# joysticks_keyboard.net
KiCad netlist of a schematic drawn in EAGLE
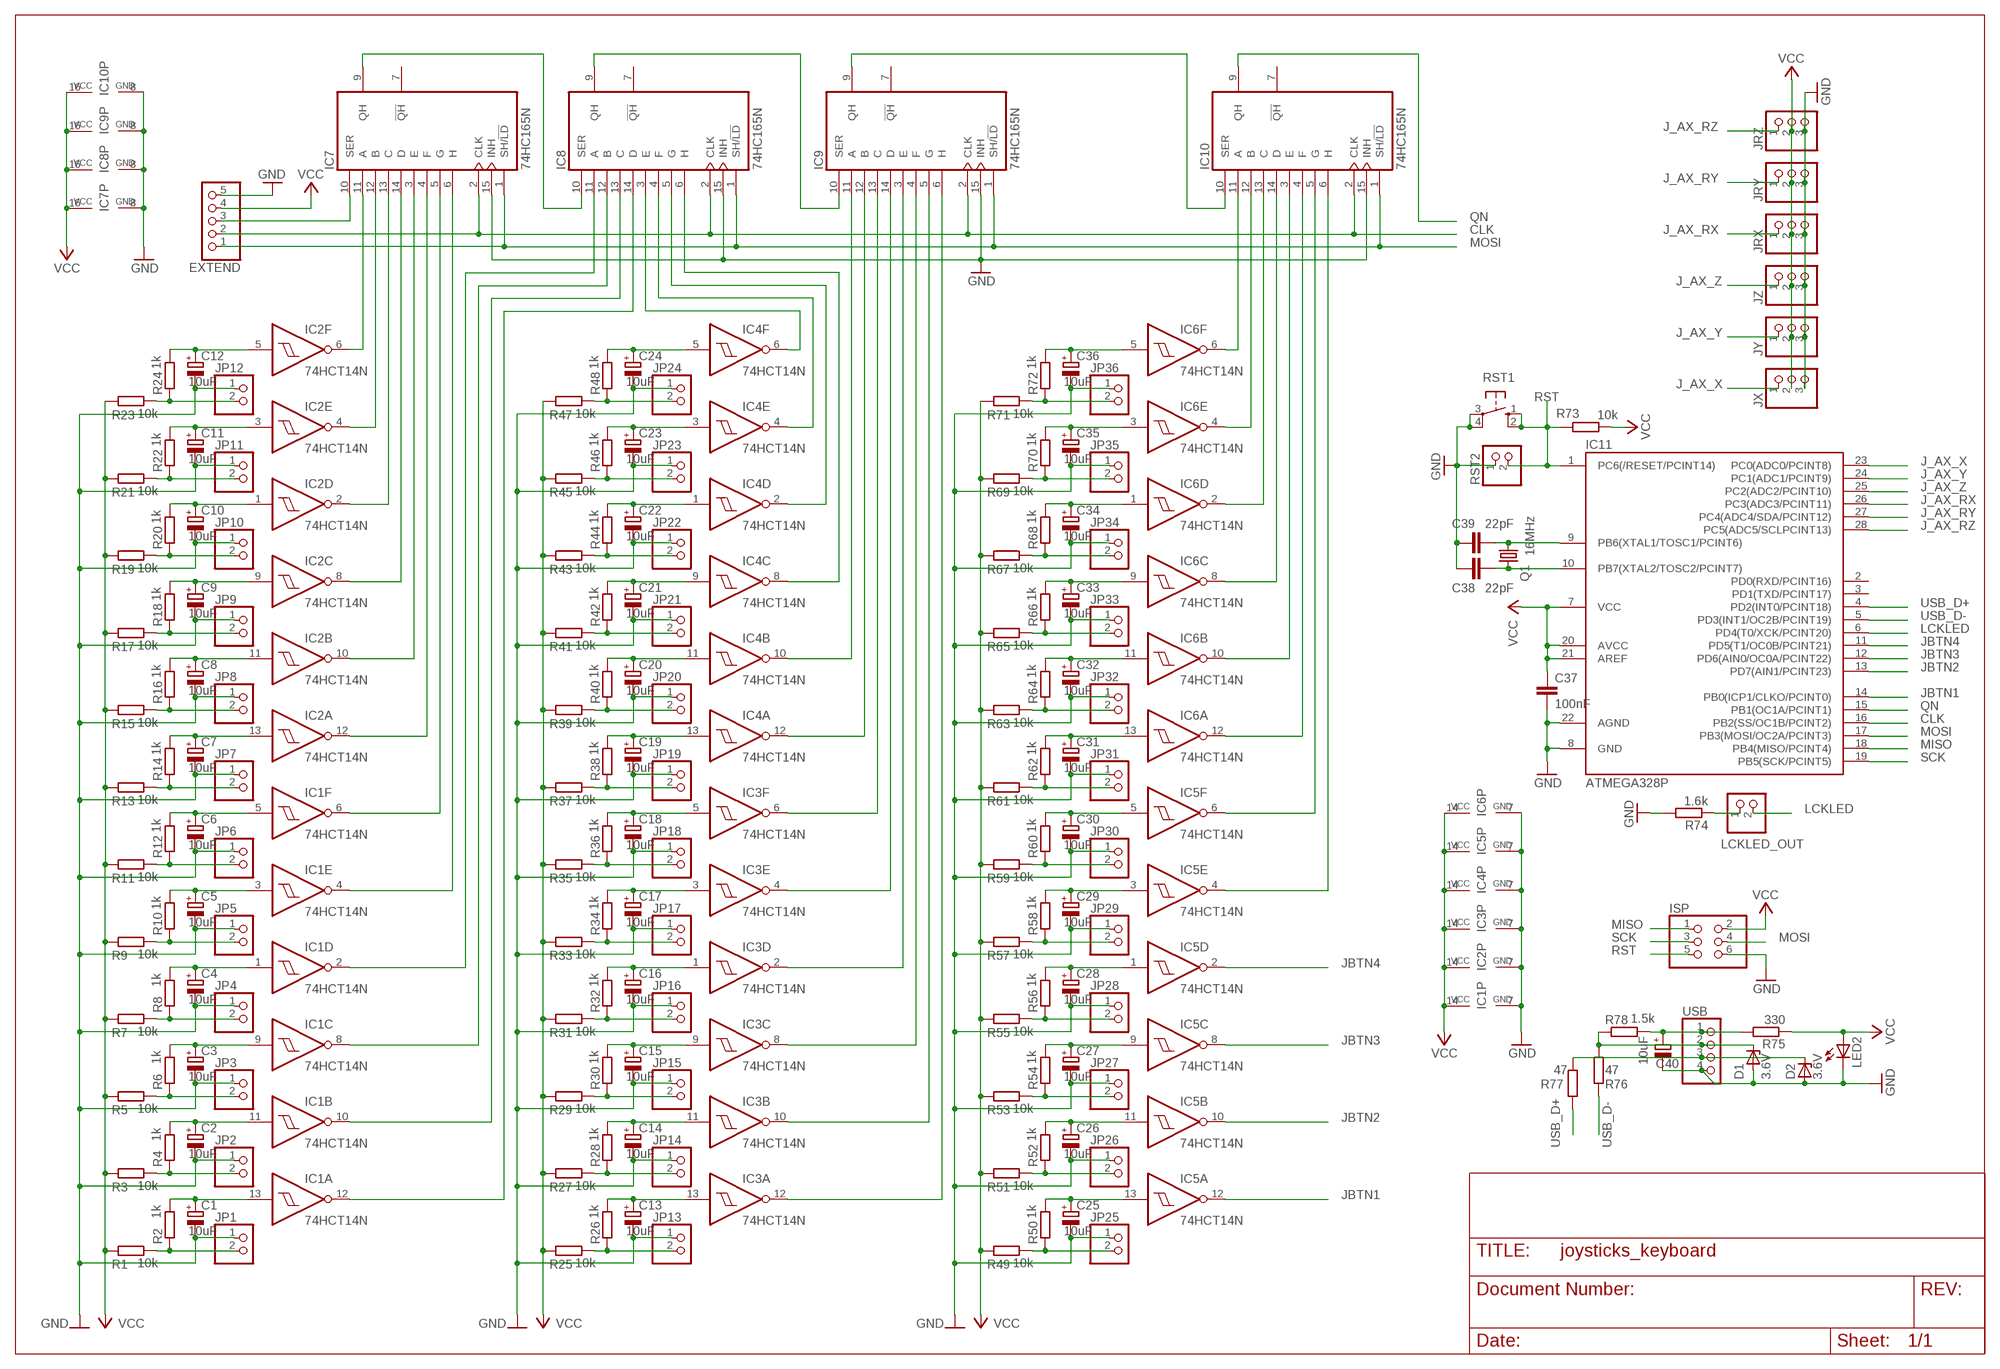
[diagram p0: schematic, sheet 1]

(export (version "E")
  (design (tool "Eeschema 10.0.6"))
  (components
    (comp (ref "C1")
      (value "10uF")
      (footprint "eagle-import:E2-5")
      (libsource (lib "eagle-import") (part "CPOL-EUE2-5"))
    )
    (comp (ref "C2")
      (value "10uF")
      (footprint "eagle-import:E2-5")
      (libsource (lib "eagle-import") (part "CPOL-EUE2-5"))
    )
    (comp (ref "C3")
      (value "10uF")
      (footprint "eagle-import:E2-5")
      (libsource (lib "eagle-import") (part "CPOL-EUE2-5"))
    )
    (comp (ref "C4")
      (value "10uF")
      (footprint "eagle-import:E2-5")
      (libsource (lib "eagle-import") (part "CPOL-EUE2-5"))
    )
    (comp (ref "C5")
      (value "10uF")
      (footprint "eagle-import:E2-5")
      (libsource (lib "eagle-import") (part "CPOL-EUE2-5"))
    )
    (comp (ref "C6")
      (value "10uF")
      (footprint "eagle-import:E2-5")
      (libsource (lib "eagle-import") (part "CPOL-EUE2-5"))
    )
    (comp (ref "C7")
      (value "10uF")
      (footprint "eagle-import:E2-5")
      (libsource (lib "eagle-import") (part "CPOL-EUE2-5"))
    )
    (comp (ref "C8")
      (value "10uF")
      (footprint "eagle-import:E2-5")
      (libsource (lib "eagle-import") (part "CPOL-EUE2-5"))
    )
    (comp (ref "C9")
      (value "10uF")
      (footprint "eagle-import:E2-5")
      (libsource (lib "eagle-import") (part "CPOL-EUE2-5"))
    )
    (comp (ref "C10")
      (value "10uF")
      (footprint "eagle-import:E2-5")
      (libsource (lib "eagle-import") (part "CPOL-EUE2-5"))
    )
    (comp (ref "C11")
      (value "10uF")
      (footprint "eagle-import:E2-5")
      (libsource (lib "eagle-import") (part "CPOL-EUE2-5"))
    )
    (comp (ref "C12")
      (value "10uF")
      (footprint "eagle-import:E2-5")
      (libsource (lib "eagle-import") (part "CPOL-EUE2-5"))
    )
    (comp (ref "C13")
      (value "10uF")
      (footprint "eagle-import:E2-5")
      (libsource (lib "eagle-import") (part "CPOL-EUE2-5"))
    )
    (comp (ref "C14")
      (value "10uF")
      (footprint "eagle-import:E2-5")
      (libsource (lib "eagle-import") (part "CPOL-EUE2-5"))
    )
    (comp (ref "C15")
      (value "10uF")
      (footprint "eagle-import:E2-5")
      (libsource (lib "eagle-import") (part "CPOL-EUE2-5"))
    )
    (comp (ref "C16")
      (value "10uF")
      (footprint "eagle-import:E2-5")
      (libsource (lib "eagle-import") (part "CPOL-EUE2-5"))
    )
    (comp (ref "C17")
      (value "10uF")
      (footprint "eagle-import:E2-5")
      (libsource (lib "eagle-import") (part "CPOL-EUE2-5"))
    )
    (comp (ref "C18")
      (value "10uF")
      (footprint "eagle-import:E2-5")
      (libsource (lib "eagle-import") (part "CPOL-EUE2-5"))
    )
    (comp (ref "C19")
      (value "10uF")
      (footprint "eagle-import:E2-5")
      (libsource (lib "eagle-import") (part "CPOL-EUE2-5"))
    )
    (comp (ref "C20")
      (value "10uF")
      (footprint "eagle-import:E2-5")
      (libsource (lib "eagle-import") (part "CPOL-EUE2-5"))
    )
    (comp (ref "C21")
      (value "10uF")
      (footprint "eagle-import:E2-5")
      (libsource (lib "eagle-import") (part "CPOL-EUE2-5"))
    )
    (comp (ref "C22")
      (value "10uF")
      (footprint "eagle-import:E2-5")
      (libsource (lib "eagle-import") (part "CPOL-EUE2-5"))
    )
    (comp (ref "C23")
      (value "10uF")
      (footprint "eagle-import:E2-5")
      (libsource (lib "eagle-import") (part "CPOL-EUE2-5"))
    )
    (comp (ref "C24")
      (value "10uF")
      (footprint "eagle-import:E2-5")
      (libsource (lib "eagle-import") (part "CPOL-EUE2-5"))
    )
    (comp (ref "C25")
      (value "10uF")
      (footprint "eagle-import:E2-5")
      (libsource (lib "eagle-import") (part "CPOL-EUE2-5"))
    )
    (comp (ref "C26")
      (value "10uF")
      (footprint "eagle-import:E2-5")
      (libsource (lib "eagle-import") (part "CPOL-EUE2-5"))
    )
    (comp (ref "C27")
      (value "10uF")
      (footprint "eagle-import:E2-5")
      (libsource (lib "eagle-import") (part "CPOL-EUE2-5"))
    )
    (comp (ref "C28")
      (value "10uF")
      (footprint "eagle-import:E2-5")
      (libsource (lib "eagle-import") (part "CPOL-EUE2-5"))
    )
    (comp (ref "C29")
      (value "10uF")
      (footprint "eagle-import:E2-5")
      (libsource (lib "eagle-import") (part "CPOL-EUE2-5"))
    )
    (comp (ref "C30")
      (value "10uF")
      (footprint "eagle-import:E2-5")
      (libsource (lib "eagle-import") (part "CPOL-EUE2-5"))
    )
    (comp (ref "C31")
      (value "10uF")
      (footprint "eagle-import:E2-5")
      (libsource (lib "eagle-import") (part "CPOL-EUE2-5"))
    )
    (comp (ref "C32")
      (value "10uF")
      (footprint "eagle-import:E2-5")
      (libsource (lib "eagle-import") (part "CPOL-EUE2-5"))
    )
    (comp (ref "C33")
      (value "10uF")
      (footprint "eagle-import:E2-5")
      (libsource (lib "eagle-import") (part "CPOL-EUE2-5"))
    )
    (comp (ref "C34")
      (value "10uF")
      (footprint "eagle-import:E2-5")
      (libsource (lib "eagle-import") (part "CPOL-EUE2-5"))
    )
    (comp (ref "C35")
      (value "10uF")
      (footprint "eagle-import:E2-5")
      (libsource (lib "eagle-import") (part "CPOL-EUE2-5"))
    )
    (comp (ref "C36")
      (value "10uF")
      (footprint "eagle-import:E2-5")
      (libsource (lib "eagle-import") (part "CPOL-EUE2-5"))
    )
    (comp (ref "C37")
      (value "100nF")
      (footprint "eagle-import:C025-024X044")
      (libsource (lib "eagle-import") (part "C-EU025-024X044"))
    )
    (comp (ref "C38")
      (value "22pF")
      (footprint "eagle-import:C025-024X044")
      (libsource (lib "eagle-import") (part "C-EU025-024X044"))
    )
    (comp (ref "C39")
      (value "22pF")
      (footprint "eagle-import:C025-024X044")
      (libsource (lib "eagle-import") (part "C-EU025-024X044"))
    )
    (comp (ref "C40")
      (value "10uF")
      (footprint "eagle-import:E2,5-6E")
      (libsource (lib "eagle-import") (part "CPOL-EUE2,5-6E"))
    )
    (comp (ref "D1")
      (value "3.6V")
      (footprint "eagle-import:ZDIO-2.5")
      (libsource (lib "eagle-import") (part "ZENER-DIODEZD-2.5"))
    )
    (comp (ref "D2")
      (value "3.6V")
      (footprint "eagle-import:ZDIO-2.5")
      (libsource (lib "eagle-import") (part "ZENER-DIODEZD-2.5"))
    )
    (comp (ref "EXTEND")
      (value "PINHD-1X5")
      (footprint "eagle-import:1X05")
      (libsource (lib "eagle-import") (part "PINHD-1X5"))
    )
    (comp (ref "IC1")
      (value "74HCT14N")
      (footprint "eagle-import:DIL14")
      (libsource (lib "eagle-import") (part "7414NHCT"))
    )
    (comp (ref "IC2")
      (value "74HCT14N")
      (footprint "eagle-import:DIL14")
      (libsource (lib "eagle-import") (part "7414NHCT"))
    )
    (comp (ref "IC3")
      (value "74HCT14N")
      (footprint "eagle-import:DIL14")
      (libsource (lib "eagle-import") (part "7414NHCT"))
    )
    (comp (ref "IC4")
      (value "74HCT14N")
      (footprint "eagle-import:DIL14")
      (libsource (lib "eagle-import") (part "7414NHCT"))
    )
    (comp (ref "IC5")
      (value "74HCT14N")
      (footprint "eagle-import:DIL14")
      (libsource (lib "eagle-import") (part "7414NHCT"))
    )
    (comp (ref "IC6")
      (value "74HCT14N")
      (footprint "eagle-import:DIL14")
      (libsource (lib "eagle-import") (part "7414NHCT"))
    )
    (comp (ref "IC7")
      (value "74HC165N")
      (footprint "eagle-import:DIL16")
      (libsource (lib "eagle-import") (part "74165NHC"))
    )
    (comp (ref "IC8")
      (value "74HC165N")
      (footprint "eagle-import:DIL16")
      (libsource (lib "eagle-import") (part "74165NHC"))
    )
    (comp (ref "IC9")
      (value "74HC165N")
      (footprint "eagle-import:DIL16")
      (libsource (lib "eagle-import") (part "74165NHC"))
    )
    (comp (ref "IC10")
      (value "74HC165N")
      (footprint "eagle-import:DIL16")
      (libsource (lib "eagle-import") (part "74165NHC"))
    )
    (comp (ref "IC11")
      (value "ATMEGA328P")
      (footprint "eagle-import:DIL28-3")
      (libsource (lib "eagle-import") (part "MEGA48/88/168-PU"))
    )
    (comp (ref "ISP")
      (value "PINHD-2X3")
      (footprint "eagle-import:2X03")
      (libsource (lib "eagle-import") (part "PINHD-2X3"))
    )
    (comp (ref "JP1")
      (value "PINHD-1X2")
      (footprint "eagle-import:1X02")
      (libsource (lib "eagle-import") (part "PINHD-1X2"))
    )
    (comp (ref "JP2")
      (value "PINHD-1X2")
      (footprint "eagle-import:1X02")
      (libsource (lib "eagle-import") (part "PINHD-1X2"))
    )
    (comp (ref "JP3")
      (value "PINHD-1X2")
      (footprint "eagle-import:1X02")
      (libsource (lib "eagle-import") (part "PINHD-1X2"))
    )
    (comp (ref "JP4")
      (value "PINHD-1X2")
      (footprint "eagle-import:1X02")
      (libsource (lib "eagle-import") (part "PINHD-1X2"))
    )
    (comp (ref "JP5")
      (value "PINHD-1X2")
      (footprint "eagle-import:1X02")
      (libsource (lib "eagle-import") (part "PINHD-1X2"))
    )
    (comp (ref "JP6")
      (value "PINHD-1X2")
      (footprint "eagle-import:1X02")
      (libsource (lib "eagle-import") (part "PINHD-1X2"))
    )
    (comp (ref "JP7")
      (value "PINHD-1X2")
      (footprint "eagle-import:1X02")
      (libsource (lib "eagle-import") (part "PINHD-1X2"))
    )
    (comp (ref "JP8")
      (value "PINHD-1X2")
      (footprint "eagle-import:1X02")
      (libsource (lib "eagle-import") (part "PINHD-1X2"))
    )
    (comp (ref "JP9")
      (value "PINHD-1X2")
      (footprint "eagle-import:1X02")
      (libsource (lib "eagle-import") (part "PINHD-1X2"))
    )
    (comp (ref "JP10")
      (value "PINHD-1X2")
      (footprint "eagle-import:1X02")
      (libsource (lib "eagle-import") (part "PINHD-1X2"))
    )
    (comp (ref "JP11")
      (value "PINHD-1X2")
      (footprint "eagle-import:1X02")
      (libsource (lib "eagle-import") (part "PINHD-1X2"))
    )
    (comp (ref "JP12")
      (value "PINHD-1X2")
      (footprint "eagle-import:1X02")
      (libsource (lib "eagle-import") (part "PINHD-1X2"))
    )
    (comp (ref "JP13")
      (value "PINHD-1X2")
      (footprint "eagle-import:1X02")
      (libsource (lib "eagle-import") (part "PINHD-1X2"))
    )
    (comp (ref "JP14")
      (value "PINHD-1X2")
      (footprint "eagle-import:1X02")
      (libsource (lib "eagle-import") (part "PINHD-1X2"))
    )
    (comp (ref "JP15")
      (value "PINHD-1X2")
      (footprint "eagle-import:1X02")
      (libsource (lib "eagle-import") (part "PINHD-1X2"))
    )
    (comp (ref "JP16")
      (value "PINHD-1X2")
      (footprint "eagle-import:1X02")
      (libsource (lib "eagle-import") (part "PINHD-1X2"))
    )
    (comp (ref "JP17")
      (value "PINHD-1X2")
      (footprint "eagle-import:1X02")
      (libsource (lib "eagle-import") (part "PINHD-1X2"))
    )
    (comp (ref "JP18")
      (value "PINHD-1X2")
      (footprint "eagle-import:1X02")
      (libsource (lib "eagle-import") (part "PINHD-1X2"))
    )
    (comp (ref "JP19")
      (value "PINHD-1X2")
      (footprint "eagle-import:1X02")
      (libsource (lib "eagle-import") (part "PINHD-1X2"))
    )
    (comp (ref "JP20")
      (value "PINHD-1X2")
      (footprint "eagle-import:1X02")
      (libsource (lib "eagle-import") (part "PINHD-1X2"))
    )
    (comp (ref "JP21")
      (value "PINHD-1X2")
      (footprint "eagle-import:1X02")
      (libsource (lib "eagle-import") (part "PINHD-1X2"))
    )
    (comp (ref "JP22")
      (value "PINHD-1X2")
      (footprint "eagle-import:1X02")
      (libsource (lib "eagle-import") (part "PINHD-1X2"))
    )
    (comp (ref "JP23")
      (value "PINHD-1X2")
      (footprint "eagle-import:1X02")
      (libsource (lib "eagle-import") (part "PINHD-1X2"))
    )
    (comp (ref "JP24")
      (value "PINHD-1X2")
      (footprint "eagle-import:1X02")
      (libsource (lib "eagle-import") (part "PINHD-1X2"))
    )
    (comp (ref "JP25")
      (value "PINHD-1X2")
      (footprint "eagle-import:1X02")
      (libsource (lib "eagle-import") (part "PINHD-1X2"))
    )
    (comp (ref "JP26")
      (value "PINHD-1X2")
      (footprint "eagle-import:1X02")
      (libsource (lib "eagle-import") (part "PINHD-1X2"))
    )
    (comp (ref "JP27")
      (value "PINHD-1X2")
      (footprint "eagle-import:1X02")
      (libsource (lib "eagle-import") (part "PINHD-1X2"))
    )
    (comp (ref "JP28")
      (value "PINHD-1X2")
      (footprint "eagle-import:1X02")
      (libsource (lib "eagle-import") (part "PINHD-1X2"))
    )
    (comp (ref "JP29")
      (value "PINHD-1X2")
      (footprint "eagle-import:1X02")
      (libsource (lib "eagle-import") (part "PINHD-1X2"))
    )
    (comp (ref "JP30")
      (value "PINHD-1X2")
      (footprint "eagle-import:1X02")
      (libsource (lib "eagle-import") (part "PINHD-1X2"))
    )
    (comp (ref "JP31")
      (value "PINHD-1X2")
      (footprint "eagle-import:1X02")
      (libsource (lib "eagle-import") (part "PINHD-1X2"))
    )
    (comp (ref "JP32")
      (value "PINHD-1X2")
      (footprint "eagle-import:1X02")
      (libsource (lib "eagle-import") (part "PINHD-1X2"))
    )
    (comp (ref "JP33")
      (value "PINHD-1X2")
      (footprint "eagle-import:1X02")
      (libsource (lib "eagle-import") (part "PINHD-1X2"))
    )
    (comp (ref "JP34")
      (value "PINHD-1X2")
      (footprint "eagle-import:1X02")
      (libsource (lib "eagle-import") (part "PINHD-1X2"))
    )
    (comp (ref "JP35")
      (value "PINHD-1X2")
      (footprint "eagle-import:1X02")
      (libsource (lib "eagle-import") (part "PINHD-1X2"))
    )
    (comp (ref "JP36")
      (value "PINHD-1X2")
      (footprint "eagle-import:1X02")
      (libsource (lib "eagle-import") (part "PINHD-1X2"))
    )
    (comp (ref "JRX")
      (value "PINHD-1X3")
      (footprint "eagle-import:1X03")
      (libsource (lib "eagle-import") (part "PINHD-1X3"))
    )
    (comp (ref "JRY")
      (value "PINHD-1X3")
      (footprint "eagle-import:1X03")
      (libsource (lib "eagle-import") (part "PINHD-1X3"))
    )
    (comp (ref "JRZ")
      (value "PINHD-1X3")
      (footprint "eagle-import:1X03")
      (libsource (lib "eagle-import") (part "PINHD-1X3"))
    )
    (comp (ref "JX")
      (value "PINHD-1X3")
      (footprint "eagle-import:1X03")
      (libsource (lib "eagle-import") (part "PINHD-1X3"))
    )
    (comp (ref "JY")
      (value "PINHD-1X3")
      (footprint "eagle-import:1X03")
      (libsource (lib "eagle-import") (part "PINHD-1X3"))
    )
    (comp (ref "JZ")
      (value "PINHD-1X3")
      (footprint "eagle-import:1X03")
      (libsource (lib "eagle-import") (part "PINHD-1X3"))
    )
    (comp (ref "LCKLED_OUT")
      (value "PINHD-1X2")
      (footprint "eagle-import:1X02")
      (libsource (lib "eagle-import") (part "PINHD-1X2"))
    )
    (comp (ref "LED2")
      (value "LEDLZR181")
      (footprint "eagle-import:LZR181")
      (libsource (lib "eagle-import") (part "LEDLZR181"))
    )
    (comp (ref "Q1")
      (value "16MHz")
      (footprint "eagle-import:HC49_S")
      (libsource (lib "eagle-import") (part "CRYSTALHC49S"))
    )
    (comp (ref "R1")
      (value "10k")
      (footprint "eagle-import:0204V")
      (libsource (lib "eagle-import") (part "R-EU_0204/2V"))
    )
    (comp (ref "R2")
      (value "1k")
      (footprint "eagle-import:0204_5")
      (libsource (lib "eagle-import") (part "R-EU_0204/5"))
    )
    (comp (ref "R3")
      (value "10k")
      (footprint "eagle-import:0204V")
      (libsource (lib "eagle-import") (part "R-EU_0204/2V"))
    )
    (comp (ref "R4")
      (value "1k")
      (footprint "eagle-import:0204_5")
      (libsource (lib "eagle-import") (part "R-EU_0204/5"))
    )
    (comp (ref "R5")
      (value "10k")
      (footprint "eagle-import:0204V")
      (libsource (lib "eagle-import") (part "R-EU_0204/2V"))
    )
    (comp (ref "R6")
      (value "1k")
      (footprint "eagle-import:0204_5")
      (libsource (lib "eagle-import") (part "R-EU_0204/5"))
    )
    (comp (ref "R7")
      (value "10k")
      (footprint "eagle-import:0204V")
      (libsource (lib "eagle-import") (part "R-EU_0204/2V"))
    )
    (comp (ref "R8")
      (value "1k")
      (footprint "eagle-import:0204_5")
      (libsource (lib "eagle-import") (part "R-EU_0204/5"))
    )
    (comp (ref "R9")
      (value "10k")
      (footprint "eagle-import:0204V")
      (libsource (lib "eagle-import") (part "R-EU_0204/2V"))
    )
    (comp (ref "R10")
      (value "1k")
      (footprint "eagle-import:0204_5")
      (libsource (lib "eagle-import") (part "R-EU_0204/5"))
    )
    (comp (ref "R11")
      (value "10k")
      (footprint "eagle-import:0204V")
      (libsource (lib "eagle-import") (part "R-EU_0204/2V"))
    )
    (comp (ref "R12")
      (value "1k")
      (footprint "eagle-import:0204_5")
      (libsource (lib "eagle-import") (part "R-EU_0204/5"))
    )
    (comp (ref "R13")
      (value "10k")
      (footprint "eagle-import:0204V")
      (libsource (lib "eagle-import") (part "R-EU_0204/2V"))
    )
    (comp (ref "R14")
      (value "1k")
      (footprint "eagle-import:0204_5")
      (libsource (lib "eagle-import") (part "R-EU_0204/5"))
    )
    (comp (ref "R15")
      (value "10k")
      (footprint "eagle-import:0204V")
      (libsource (lib "eagle-import") (part "R-EU_0204/2V"))
    )
    (comp (ref "R16")
      (value "1k")
      (footprint "eagle-import:0204_5")
      (libsource (lib "eagle-import") (part "R-EU_0204/5"))
    )
    (comp (ref "R17")
      (value "10k")
      (footprint "eagle-import:0204V")
      (libsource (lib "eagle-import") (part "R-EU_0204/2V"))
    )
    (comp (ref "R18")
      (value "1k")
      (footprint "eagle-import:0204_5")
      (libsource (lib "eagle-import") (part "R-EU_0204/5"))
    )
    (comp (ref "R19")
      (value "10k")
      (footprint "eagle-import:0204V")
      (libsource (lib "eagle-import") (part "R-EU_0204/2V"))
    )
    (comp (ref "R20")
      (value "1k")
      (footprint "eagle-import:0204_5")
      (libsource (lib "eagle-import") (part "R-EU_0204/5"))
    )
    (comp (ref "R21")
      (value "10k")
      (footprint "eagle-import:0204V")
      (libsource (lib "eagle-import") (part "R-EU_0204/2V"))
    )
    (comp (ref "R22")
      (value "1k")
      (footprint "eagle-import:0204_5")
      (libsource (lib "eagle-import") (part "R-EU_0204/5"))
    )
    (comp (ref "R23")
      (value "10k")
      (footprint "eagle-import:0204V")
      (libsource (lib "eagle-import") (part "R-EU_0204/2V"))
    )
    (comp (ref "R24")
      (value "1k")
      (footprint "eagle-import:0204_5")
      (libsource (lib "eagle-import") (part "R-EU_0204/5"))
    )
    (comp (ref "R25")
      (value "10k")
      (footprint "eagle-import:0204V")
      (libsource (lib "eagle-import") (part "R-EU_0204/2V"))
    )
    (comp (ref "R26")
      (value "1k")
      (footprint "eagle-import:0204_5")
      (libsource (lib "eagle-import") (part "R-EU_0204/5"))
    )
    (comp (ref "R27")
      (value "10k")
      (footprint "eagle-import:0204V")
      (libsource (lib "eagle-import") (part "R-EU_0204/2V"))
    )
    (comp (ref "R28")
      (value "1k")
      (footprint "eagle-import:0204_5")
      (libsource (lib "eagle-import") (part "R-EU_0204/5"))
    )
    (comp (ref "R29")
      (value "10k")
      (footprint "eagle-import:0204V")
      (libsource (lib "eagle-import") (part "R-EU_0204/2V"))
    )
    (comp (ref "R30")
      (value "1k")
      (footprint "eagle-import:0204_5")
      (libsource (lib "eagle-import") (part "R-EU_0204/5"))
    )
    (comp (ref "R31")
      (value "10k")
      (footprint "eagle-import:0204V")
      (libsource (lib "eagle-import") (part "R-EU_0204/2V"))
    )
    (comp (ref "R32")
      (value "1k")
      (footprint "eagle-import:0204_5")
      (libsource (lib "eagle-import") (part "R-EU_0204/5"))
    )
    (comp (ref "R33")
      (value "10k")
      (footprint "eagle-import:0204V")
      (libsource (lib "eagle-import") (part "R-EU_0204/2V"))
    )
    (comp (ref "R34")
      (value "1k")
      (footprint "eagle-import:0204_5")
      (libsource (lib "eagle-import") (part "R-EU_0204/5"))
    )
    (comp (ref "R35")
      (value "10k")
      (footprint "eagle-import:0204V")
      (libsource (lib "eagle-import") (part "R-EU_0204/2V"))
    )
    (comp (ref "R36")
      (value "1k")
      (footprint "eagle-import:0204_5")
      (libsource (lib "eagle-import") (part "R-EU_0204/5"))
    )
    (comp (ref "R37")
      (value "10k")
      (footprint "eagle-import:0204V")
      (libsource (lib "eagle-import") (part "R-EU_0204/2V"))
    )
    (comp (ref "R38")
      (value "1k")
      (footprint "eagle-import:0204_5")
      (libsource (lib "eagle-import") (part "R-EU_0204/5"))
    )
    (comp (ref "R39")
      (value "10k")
      (footprint "eagle-import:0204V")
      (libsource (lib "eagle-import") (part "R-EU_0204/2V"))
    )
    (comp (ref "R40")
      (value "1k")
      (footprint "eagle-import:0204_5")
      (libsource (lib "eagle-import") (part "R-EU_0204/5"))
    )
    (comp (ref "R41")
      (value "10k")
      (footprint "eagle-import:0204V")
      (libsource (lib "eagle-import") (part "R-EU_0204/2V"))
    )
    (comp (ref "R42")
      (value "1k")
      (footprint "eagle-import:0204_5")
      (libsource (lib "eagle-import") (part "R-EU_0204/5"))
    )
    (comp (ref "R43")
      (value "10k")
      (footprint "eagle-import:0204V")
      (libsource (lib "eagle-import") (part "R-EU_0204/2V"))
    )
    (comp (ref "R44")
      (value "1k")
      (footprint "eagle-import:0204_5")
      (libsource (lib "eagle-import") (part "R-EU_0204/5"))
    )
    (comp (ref "R45")
      (value "10k")
      (footprint "eagle-import:0204V")
      (libsource (lib "eagle-import") (part "R-EU_0204/2V"))
    )
    (comp (ref "R46")
      (value "1k")
      (footprint "eagle-import:0204_5")
      (libsource (lib "eagle-import") (part "R-EU_0204/5"))
    )
    (comp (ref "R47")
      (value "10k")
      (footprint "eagle-import:0204V")
      (libsource (lib "eagle-import") (part "R-EU_0204/2V"))
    )
    (comp (ref "R48")
      (value "1k")
      (footprint "eagle-import:0204_5")
      (libsource (lib "eagle-import") (part "R-EU_0204/5"))
    )
    (comp (ref "R49")
      (value "10k")
      (footprint "eagle-import:0204V")
      (libsource (lib "eagle-import") (part "R-EU_0204/2V"))
    )
    (comp (ref "R50")
      (value "1k")
      (footprint "eagle-import:0204_5")
      (libsource (lib "eagle-import") (part "R-EU_0204/5"))
    )
    (comp (ref "R51")
      (value "10k")
      (footprint "eagle-import:0204V")
      (libsource (lib "eagle-import") (part "R-EU_0204/2V"))
    )
    (comp (ref "R52")
      (value "1k")
      (footprint "eagle-import:0204_5")
      (libsource (lib "eagle-import") (part "R-EU_0204/5"))
    )
    (comp (ref "R53")
      (value "10k")
      (footprint "eagle-import:0204V")
      (libsource (lib "eagle-import") (part "R-EU_0204/2V"))
    )
    (comp (ref "R54")
      (value "1k")
      (footprint "eagle-import:0204_5")
      (libsource (lib "eagle-import") (part "R-EU_0204/5"))
    )
    (comp (ref "R55")
      (value "10k")
      (footprint "eagle-import:0204V")
      (libsource (lib "eagle-import") (part "R-EU_0204/2V"))
    )
    (comp (ref "R56")
      (value "1k")
      (footprint "eagle-import:0204_5")
      (libsource (lib "eagle-import") (part "R-EU_0204/5"))
    )
    (comp (ref "R57")
      (value "10k")
      (footprint "eagle-import:0204V")
      (libsource (lib "eagle-import") (part "R-EU_0204/2V"))
    )
    (comp (ref "R58")
      (value "1k")
      (footprint "eagle-import:0204_5")
      (libsource (lib "eagle-import") (part "R-EU_0204/5"))
    )
    (comp (ref "R59")
      (value "10k")
      (footprint "eagle-import:0204V")
      (libsource (lib "eagle-import") (part "R-EU_0204/2V"))
    )
    (comp (ref "R60")
      (value "1k")
      (footprint "eagle-import:0204_5")
      (libsource (lib "eagle-import") (part "R-EU_0204/5"))
    )
    (comp (ref "R61")
      (value "10k")
      (footprint "eagle-import:0204V")
      (libsource (lib "eagle-import") (part "R-EU_0204/2V"))
    )
    (comp (ref "R62")
      (value "1k")
      (footprint "eagle-import:0204_5")
      (libsource (lib "eagle-import") (part "R-EU_0204/5"))
    )
    (comp (ref "R63")
      (value "10k")
      (footprint "eagle-import:0204V")
      (libsource (lib "eagle-import") (part "R-EU_0204/2V"))
    )
    (comp (ref "R64")
      (value "1k")
      (footprint "eagle-import:0204_5")
      (libsource (lib "eagle-import") (part "R-EU_0204/5"))
    )
    (comp (ref "R65")
      (value "10k")
      (footprint "eagle-import:0204V")
      (libsource (lib "eagle-import") (part "R-EU_0204/2V"))
    )
    (comp (ref "R66")
      (value "1k")
      (footprint "eagle-import:0204_5")
      (libsource (lib "eagle-import") (part "R-EU_0204/5"))
    )
    (comp (ref "R67")
      (value "10k")
      (footprint "eagle-import:0204V")
      (libsource (lib "eagle-import") (part "R-EU_0204/2V"))
    )
    (comp (ref "R68")
      (value "1k")
      (footprint "eagle-import:0204_5")
      (libsource (lib "eagle-import") (part "R-EU_0204/5"))
    )
    (comp (ref "R69")
      (value "10k")
      (footprint "eagle-import:0204V")
      (libsource (lib "eagle-import") (part "R-EU_0204/2V"))
    )
    (comp (ref "R70")
      (value "1k")
      (footprint "eagle-import:0204_5")
      (libsource (lib "eagle-import") (part "R-EU_0204/5"))
    )
    (comp (ref "R71")
      (value "10k")
      (footprint "eagle-import:0204V")
      (libsource (lib "eagle-import") (part "R-EU_0204/2V"))
    )
    (comp (ref "R72")
      (value "1k")
      (footprint "eagle-import:0204_5")
      (libsource (lib "eagle-import") (part "R-EU_0204/5"))
    )
    (comp (ref "R73")
      (value "10k")
      (footprint "eagle-import:0204_7")
      (libsource (lib "eagle-import") (part "R-EU_0204/7"))
    )
    (comp (ref "R74")
      (value "1.6k")
      (footprint "eagle-import:0204_7")
      (libsource (lib "eagle-import") (part "R-EU_0204/7"))
    )
    (comp (ref "R75")
      (value "330")
      (footprint "eagle-import:0204_7")
      (libsource (lib "eagle-import") (part "R-EU_0204/7"))
    )
    (comp (ref "R76")
      (value "47")
      (footprint "eagle-import:0204_7")
      (libsource (lib "eagle-import") (part "R-EU_0204/7"))
    )
    (comp (ref "R77")
      (value "47")
      (footprint "eagle-import:0204_7")
      (libsource (lib "eagle-import") (part "R-EU_0204/7"))
    )
    (comp (ref "R78")
      (value "1.5k")
      (footprint "eagle-import:0204_7")
      (libsource (lib "eagle-import") (part "R-EU_0204/7"))
    )
    (comp (ref "RST1")
      (value "10-XX")
      (footprint "eagle-import:B3F-10XX")
      (fields (field (name "MPN") "B3F-1000"))
      (libsource (lib "eagle-import") (part "10-XX"))
    )
    (comp (ref "RST2")
      (value "PINHD-1X2")
      (footprint "eagle-import:1X02")
      (libsource (lib "eagle-import") (part "PINHD-1X2"))
    )
    (comp (ref "USB")
      (value "PINHD-1X4")
      (footprint "eagle-import:1X04")
      (libsource (lib "eagle-import") (part "PINHD-1X4"))
    )
  )
  (nets
    (net (code "1") (name "/CLK") (class "Default")
      (node (ref "EXTEND") (pin "2") (pinfunction "2_2") (pintype "passive"))
      (node (ref "IC10") (pin "2") (pinfunction "CLK_2") (pintype "input"))
      (node (ref "IC11") (pin "16") (pinfunction "PB2(SS/OC1B/PCINT2)_16") (pintype "bidirectional"))
      (node (ref "IC7") (pin "2") (pinfunction "CLK_2") (pintype "input"))
      (node (ref "IC8") (pin "2") (pinfunction "CLK_2") (pintype "input"))
      (node (ref "IC9") (pin "2") (pinfunction "CLK_2") (pintype "input"))
    )
    (net (code "2") (name "/JBTN1") (class "Default")
      (node (ref "IC11") (pin "14") (pinfunction "PB0(ICP1/CLKO/PCINT0)_14") (pintype "bidirectional"))
      (node (ref "IC5") (pin "12") (pinfunction "O_12") (pintype "output"))
    )
    (net (code "3") (name "/JBTN2") (class "Default")
      (node (ref "IC11") (pin "13") (pinfunction "PD7(AIN1/PCINT23)_13") (pintype "bidirectional"))
      (node (ref "IC5") (pin "10") (pinfunction "O_10") (pintype "output"))
    )
    (net (code "4") (name "/JBTN3") (class "Default")
      (node (ref "IC11") (pin "12") (pinfunction "PD6(AIN0/OC0A/PCINT22)_12") (pintype "bidirectional"))
      (node (ref "IC5") (pin "8") (pinfunction "O_8") (pintype "output"))
    )
    (net (code "5") (name "/JBTN4") (class "Default")
      (node (ref "IC11") (pin "11") (pinfunction "PD5(T1/OC0B/PCINT21)_11") (pintype "bidirectional"))
      (node (ref "IC5") (pin "2") (pinfunction "O_2") (pintype "output"))
    )
    (net (code "6") (name "/J_AX_RX") (class "Default")
      (node (ref "IC11") (pin "26") (pinfunction "PC3(ADC3/PCINT11)_26") (pintype "bidirectional"))
      (node (ref "JRX") (pin "1") (pinfunction "1_1") (pintype "passive"))
    )
    (net (code "7") (name "/J_AX_RY") (class "Default")
      (node (ref "IC11") (pin "27") (pinfunction "PC4(ADC4/SDA/PCINT12)_27") (pintype "bidirectional"))
      (node (ref "JRY") (pin "1") (pinfunction "1_1") (pintype "passive"))
    )
    (net (code "8") (name "/J_AX_RZ") (class "Default")
      (node (ref "IC11") (pin "28") (pinfunction "PC5(ADC5/SCLPCINT13)_28") (pintype "bidirectional"))
      (node (ref "JRZ") (pin "1") (pinfunction "1_1") (pintype "passive"))
    )
    (net (code "9") (name "/J_AX_X") (class "Default")
      (node (ref "IC11") (pin "23") (pinfunction "PC0(ADC0/PCINT8)_23") (pintype "bidirectional"))
      (node (ref "JX") (pin "1") (pinfunction "1_1") (pintype "passive"))
    )
    (net (code "10") (name "/J_AX_Y") (class "Default")
      (node (ref "IC11") (pin "24") (pinfunction "PC1(ADC1/PCINT9)_24") (pintype "bidirectional"))
      (node (ref "JY") (pin "1") (pinfunction "1_1") (pintype "passive"))
    )
    (net (code "11") (name "/J_AX_Z") (class "Default")
      (node (ref "IC11") (pin "25") (pinfunction "PC2(ADC2/PCINT10)_25") (pintype "bidirectional"))
      (node (ref "JZ") (pin "1") (pinfunction "1_1") (pintype "passive"))
    )
    (net (code "12") (name "/LCKLED") (class "Default")
      (node (ref "IC11") (pin "6") (pinfunction "PD4(T0/XCK/PCINT20)_6") (pintype "bidirectional"))
      (node (ref "LCKLED_OUT") (pin "2") (pinfunction "2_2") (pintype "passive"))
    )
    (net (code "13") (name "/MISO") (class "Default")
      (node (ref "IC11") (pin "18") (pinfunction "PB4(MISO/PCINT4)_18") (pintype "bidirectional"))
      (node (ref "ISP") (pin "1") (pinfunction "1_1") (pintype "passive"))
    )
    (net (code "14") (name "/MOSI") (class "Default")
      (node (ref "EXTEND") (pin "1") (pinfunction "1_1") (pintype "passive"))
      (node (ref "IC10") (pin "1") (pinfunction "SH/~{LD}_1") (pintype "input"))
      (node (ref "IC11") (pin "17") (pinfunction "PB3(MOSI/OC2A/PCINT3)_17") (pintype "bidirectional"))
      (node (ref "IC7") (pin "1") (pinfunction "SH/~{LD}_1") (pintype "input"))
      (node (ref "IC8") (pin "1") (pinfunction "SH/~{LD}_1") (pintype "input"))
      (node (ref "IC9") (pin "1") (pinfunction "SH/~{LD}_1") (pintype "input"))
      (node (ref "ISP") (pin "4") (pinfunction "4_4") (pintype "passive"))
    )
    (net (code "15") (name "/QN") (class "Default")
      (node (ref "IC10") (pin "9") (pinfunction "QH_9") (pintype "output"))
      (node (ref "IC11") (pin "15") (pinfunction "PB1(OC1A/PCINT1)_15") (pintype "bidirectional"))
    )
    (net (code "16") (name "/RST") (class "Default")
      (node (ref "IC11") (pin "1") (pinfunction "PC6(/RESET/PCINT14)_1") (pintype "bidirectional"))
      (node (ref "ISP") (pin "5") (pinfunction "5_5") (pintype "passive"))
      (node (ref "R73") (pin "2") (pinfunction "2_2") (pintype "passive"))
      (node (ref "RST1") (pin "1") (pinfunction "S_1") (pintype "passive"))
      (node (ref "RST1") (pin "2") (pinfunction "S1_2") (pintype "passive"))
      (node (ref "RST2") (pin "2") (pinfunction "2_2") (pintype "passive"))
    )
    (net (code "17") (name "/SCK") (class "Default")
      (node (ref "IC11") (pin "19") (pinfunction "PB5(SCK/PCINT5)_19") (pintype "bidirectional"))
      (node (ref "ISP") (pin "3") (pinfunction "3_3") (pintype "passive"))
    )
    (net (code "18") (name "/USB_D+") (class "Default")
      (node (ref "IC11") (pin "4") (pinfunction "PD2(INT0/PCINT18)_4") (pintype "bidirectional"))
      (node (ref "R77") (pin "2") (pinfunction "2_2") (pintype "passive"))
    )
    (net (code "19") (name "/USB_D-") (class "Default")
      (node (ref "IC11") (pin "5") (pinfunction "PD3(INT1/OC2B/PCINT19)_5") (pintype "bidirectional"))
      (node (ref "R76") (pin "2") (pinfunction "2_2") (pintype "passive"))
    )
    (net (code "20") (name "GND") (class "Default")
      (node (ref "C1") (pin "-") (pinfunction "-_-") (pintype "passive"))
      (node (ref "C10") (pin "-") (pinfunction "-_-") (pintype "passive"))
      (node (ref "C11") (pin "-") (pinfunction "-_-") (pintype "passive"))
      (node (ref "C12") (pin "-") (pinfunction "-_-") (pintype "passive"))
      (node (ref "C13") (pin "-") (pinfunction "-_-") (pintype "passive"))
      (node (ref "C14") (pin "-") (pinfunction "-_-") (pintype "passive"))
      (node (ref "C15") (pin "-") (pinfunction "-_-") (pintype "passive"))
      (node (ref "C16") (pin "-") (pinfunction "-_-") (pintype "passive"))
      (node (ref "C17") (pin "-") (pinfunction "-_-") (pintype "passive"))
      (node (ref "C18") (pin "-") (pinfunction "-_-") (pintype "passive"))
      (node (ref "C19") (pin "-") (pinfunction "-_-") (pintype "passive"))
      (node (ref "C2") (pin "-") (pinfunction "-_-") (pintype "passive"))
      (node (ref "C20") (pin "-") (pinfunction "-_-") (pintype "passive"))
      (node (ref "C21") (pin "-") (pinfunction "-_-") (pintype "passive"))
      (node (ref "C22") (pin "-") (pinfunction "-_-") (pintype "passive"))
      (node (ref "C23") (pin "-") (pinfunction "-_-") (pintype "passive"))
      (node (ref "C24") (pin "-") (pinfunction "-_-") (pintype "passive"))
      (node (ref "C25") (pin "-") (pinfunction "-_-") (pintype "passive"))
      (node (ref "C26") (pin "-") (pinfunction "-_-") (pintype "passive"))
      (node (ref "C27") (pin "-") (pinfunction "-_-") (pintype "passive"))
      (node (ref "C28") (pin "-") (pinfunction "-_-") (pintype "passive"))
      (node (ref "C29") (pin "-") (pinfunction "-_-") (pintype "passive"))
      (node (ref "C3") (pin "-") (pinfunction "-_-") (pintype "passive"))
      (node (ref "C30") (pin "-") (pinfunction "-_-") (pintype "passive"))
      (node (ref "C31") (pin "-") (pinfunction "-_-") (pintype "passive"))
      (node (ref "C32") (pin "-") (pinfunction "-_-") (pintype "passive"))
      (node (ref "C33") (pin "-") (pinfunction "-_-") (pintype "passive"))
      (node (ref "C34") (pin "-") (pinfunction "-_-") (pintype "passive"))
      (node (ref "C35") (pin "-") (pinfunction "-_-") (pintype "passive"))
      (node (ref "C36") (pin "-") (pinfunction "-_-") (pintype "passive"))
      (node (ref "C37") (pin "2") (pinfunction "2_2") (pintype "passive"))
      (node (ref "C38") (pin "1") (pinfunction "1_1") (pintype "passive"))
      (node (ref "C39") (pin "1") (pinfunction "1_1") (pintype "passive"))
      (node (ref "C4") (pin "-") (pinfunction "-_-") (pintype "passive"))
      (node (ref "C40") (pin "-") (pinfunction "-_-") (pintype "passive"))
      (node (ref "C5") (pin "-") (pinfunction "-_-") (pintype "passive"))
      (node (ref "C6") (pin "-") (pinfunction "-_-") (pintype "passive"))
      (node (ref "C7") (pin "-") (pinfunction "-_-") (pintype "passive"))
      (node (ref "C8") (pin "-") (pinfunction "-_-") (pintype "passive"))
      (node (ref "C9") (pin "-") (pinfunction "-_-") (pintype "passive"))
      (node (ref "D1") (pin "A") (pinfunction "A_A") (pintype "passive"))
      (node (ref "D2") (pin "A") (pinfunction "A_A") (pintype "passive"))
      (node (ref "EXTEND") (pin "5") (pinfunction "5_5") (pintype "passive"))
      (node (ref "IC1") (pin "7") (pinfunction "GND_7") (pintype "power_in"))
      (node (ref "IC10") (pin "15") (pinfunction "INH_15") (pintype "input"))
      (node (ref "IC10") (pin "8") (pinfunction "GND_8") (pintype "power_in"))
      (node (ref "IC11") (pin "22") (pinfunction "AGND_22") (pintype "power_in"))
      (node (ref "IC11") (pin "8") (pinfunction "GND_8") (pintype "power_in"))
      (node (ref "IC2") (pin "7") (pinfunction "GND_7") (pintype "power_in"))
      (node (ref "IC3") (pin "7") (pinfunction "GND_7") (pintype "power_in"))
      (node (ref "IC4") (pin "7") (pinfunction "GND_7") (pintype "power_in"))
      (node (ref "IC5") (pin "7") (pinfunction "GND_7") (pintype "power_in"))
      (node (ref "IC6") (pin "7") (pinfunction "GND_7") (pintype "power_in"))
      (node (ref "IC7") (pin "15") (pinfunction "INH_15") (pintype "input"))
      (node (ref "IC7") (pin "8") (pinfunction "GND_8") (pintype "power_in"))
      (node (ref "IC8") (pin "15") (pinfunction "INH_15") (pintype "input"))
      (node (ref "IC8") (pin "8") (pinfunction "GND_8") (pintype "power_in"))
      (node (ref "IC9") (pin "15") (pinfunction "INH_15") (pintype "input"))
      (node (ref "IC9") (pin "8") (pinfunction "GND_8") (pintype "power_in"))
      (node (ref "ISP") (pin "6") (pinfunction "6_6") (pintype "passive"))
      (node (ref "JP1") (pin "1") (pinfunction "1_1") (pintype "passive"))
      (node (ref "JP10") (pin "1") (pinfunction "1_1") (pintype "passive"))
      (node (ref "JP11") (pin "1") (pinfunction "1_1") (pintype "passive"))
      (node (ref "JP12") (pin "1") (pinfunction "1_1") (pintype "passive"))
      (node (ref "JP13") (pin "1") (pinfunction "1_1") (pintype "passive"))
      (node (ref "JP14") (pin "1") (pinfunction "1_1") (pintype "passive"))
      (node (ref "JP15") (pin "1") (pinfunction "1_1") (pintype "passive"))
      (node (ref "JP16") (pin "1") (pinfunction "1_1") (pintype "passive"))
      (node (ref "JP17") (pin "1") (pinfunction "1_1") (pintype "passive"))
      (node (ref "JP18") (pin "1") (pinfunction "1_1") (pintype "passive"))
      (node (ref "JP19") (pin "1") (pinfunction "1_1") (pintype "passive"))
      (node (ref "JP2") (pin "1") (pinfunction "1_1") (pintype "passive"))
      (node (ref "JP20") (pin "1") (pinfunction "1_1") (pintype "passive"))
      (node (ref "JP21") (pin "1") (pinfunction "1_1") (pintype "passive"))
      (node (ref "JP22") (pin "1") (pinfunction "1_1") (pintype "passive"))
      (node (ref "JP23") (pin "1") (pinfunction "1_1") (pintype "passive"))
      (node (ref "JP24") (pin "1") (pinfunction "1_1") (pintype "passive"))
      (node (ref "JP25") (pin "1") (pinfunction "1_1") (pintype "passive"))
      (node (ref "JP26") (pin "1") (pinfunction "1_1") (pintype "passive"))
      (node (ref "JP27") (pin "1") (pinfunction "1_1") (pintype "passive"))
      (node (ref "JP28") (pin "1") (pinfunction "1_1") (pintype "passive"))
      (node (ref "JP29") (pin "1") (pinfunction "1_1") (pintype "passive"))
      (node (ref "JP3") (pin "1") (pinfunction "1_1") (pintype "passive"))
      (node (ref "JP30") (pin "1") (pinfunction "1_1") (pintype "passive"))
      (node (ref "JP31") (pin "1") (pinfunction "1_1") (pintype "passive"))
      (node (ref "JP32") (pin "1") (pinfunction "1_1") (pintype "passive"))
      (node (ref "JP33") (pin "1") (pinfunction "1_1") (pintype "passive"))
      (node (ref "JP34") (pin "1") (pinfunction "1_1") (pintype "passive"))
      (node (ref "JP35") (pin "1") (pinfunction "1_1") (pintype "passive"))
      (node (ref "JP36") (pin "1") (pinfunction "1_1") (pintype "passive"))
      (node (ref "JP4") (pin "1") (pinfunction "1_1") (pintype "passive"))
      (node (ref "JP5") (pin "1") (pinfunction "1_1") (pintype "passive"))
      (node (ref "JP6") (pin "1") (pinfunction "1_1") (pintype "passive"))
      (node (ref "JP7") (pin "1") (pinfunction "1_1") (pintype "passive"))
      (node (ref "JP8") (pin "1") (pinfunction "1_1") (pintype "passive"))
      (node (ref "JP9") (pin "1") (pinfunction "1_1") (pintype "passive"))
      (node (ref "JRX") (pin "3") (pinfunction "3_3") (pintype "passive"))
      (node (ref "JRY") (pin "3") (pinfunction "3_3") (pintype "passive"))
      (node (ref "JRZ") (pin "3") (pinfunction "3_3") (pintype "passive"))
      (node (ref "JX") (pin "3") (pinfunction "3_3") (pintype "passive"))
      (node (ref "JY") (pin "3") (pinfunction "3_3") (pintype "passive"))
      (node (ref "JZ") (pin "3") (pinfunction "3_3") (pintype "passive"))
      (node (ref "LED2") (pin "K") (pinfunction "C_K") (pintype "passive"))
      (node (ref "R74") (pin "2") (pinfunction "2_2") (pintype "passive"))
      (node (ref "RST1") (pin "3") (pinfunction "P_3") (pintype "passive"))
      (node (ref "RST1") (pin "4") (pinfunction "P1_4") (pintype "passive"))
      (node (ref "RST2") (pin "1") (pinfunction "1_1") (pintype "passive"))
      (node (ref "USB") (pin "4") (pinfunction "4_4") (pintype "passive"))
    )
    (net (code "21") (name "Net-(C40-Pad+)") (class "Default")
      (node (ref "C40") (pin "+") (pinfunction "+_+") (pintype "passive"))
      (node (ref "R75") (pin "2") (pinfunction "2_2") (pintype "passive"))
      (node (ref "R78") (pin "2") (pinfunction "2_2") (pintype "passive"))
      (node (ref "USB") (pin "1") (pinfunction "1_1") (pintype "passive"))
    )
    (net (code "22") (name "Net-(D1-PadC)") (class "Default")
      (node (ref "D1") (pin "C") (pinfunction "C_C") (pintype "passive"))
      (node (ref "R76") (pin "1") (pinfunction "1_1") (pintype "passive"))
      (node (ref "R78") (pin "1") (pinfunction "1_1") (pintype "passive"))
      (node (ref "USB") (pin "2") (pinfunction "2_2") (pintype "passive"))
    )
    (net (code "23") (name "Net-(D2-PadC)") (class "Default")
      (node (ref "D2") (pin "C") (pinfunction "C_C") (pintype "passive"))
      (node (ref "R77") (pin "1") (pinfunction "1_1") (pintype "passive"))
      (node (ref "USB") (pin "3") (pinfunction "3_3") (pintype "passive"))
    )
    (net (code "24") (name "Net-(IC1A-I)") (class "Default")
      (node (ref "C1") (pin "+") (pinfunction "+_+") (pintype "passive"))
      (node (ref "IC1") (pin "13") (pinfunction "I_13") (pintype "input"))
      (node (ref "R2") (pin "2") (pinfunction "2_2") (pintype "passive"))
    )
    (net (code "25") (name "Net-(IC1A-O)") (class "Default")
      (node (ref "IC1") (pin "12") (pinfunction "O_12") (pintype "output"))
      (node (ref "IC8") (pin "14") (pinfunction "D_14") (pintype "input"))
    )
    (net (code "26") (name "Net-(IC1B-I)") (class "Default")
      (node (ref "C2") (pin "+") (pinfunction "+_+") (pintype "passive"))
      (node (ref "IC1") (pin "11") (pinfunction "I_11") (pintype "input"))
      (node (ref "R4") (pin "2") (pinfunction "2_2") (pintype "passive"))
    )
    (net (code "27") (name "Net-(IC1B-O)") (class "Default")
      (node (ref "IC1") (pin "10") (pinfunction "O_10") (pintype "output"))
      (node (ref "IC8") (pin "13") (pinfunction "C_13") (pintype "input"))
    )
    (net (code "28") (name "Net-(IC1C-I)") (class "Default")
      (node (ref "C3") (pin "+") (pinfunction "+_+") (pintype "passive"))
      (node (ref "IC1") (pin "9") (pinfunction "I_9") (pintype "input"))
      (node (ref "R6") (pin "2") (pinfunction "2_2") (pintype "passive"))
    )
    (net (code "29") (name "Net-(IC1C-O)") (class "Default")
      (node (ref "IC1") (pin "8") (pinfunction "O_8") (pintype "output"))
      (node (ref "IC8") (pin "12") (pinfunction "B_12") (pintype "input"))
    )
    (net (code "30") (name "Net-(IC1D-I)") (class "Default")
      (node (ref "C4") (pin "+") (pinfunction "+_+") (pintype "passive"))
      (node (ref "IC1") (pin "1") (pinfunction "I_1") (pintype "input"))
      (node (ref "R8") (pin "2") (pinfunction "2_2") (pintype "passive"))
    )
    (net (code "31") (name "Net-(IC1D-O)") (class "Default")
      (node (ref "IC1") (pin "2") (pinfunction "O_2") (pintype "output"))
      (node (ref "IC8") (pin "11") (pinfunction "A_11") (pintype "input"))
    )
    (net (code "32") (name "Net-(IC1E-I)") (class "Default")
      (node (ref "C5") (pin "+") (pinfunction "+_+") (pintype "passive"))
      (node (ref "IC1") (pin "3") (pinfunction "I_3") (pintype "input"))
      (node (ref "R10") (pin "2") (pinfunction "2_2") (pintype "passive"))
    )
    (net (code "33") (name "Net-(IC1E-O)") (class "Default")
      (node (ref "IC1") (pin "4") (pinfunction "O_4") (pintype "output"))
      (node (ref "IC7") (pin "6") (pinfunction "H_6") (pintype "input"))
    )
    (net (code "34") (name "Net-(IC1F-I)") (class "Default")
      (node (ref "C6") (pin "+") (pinfunction "+_+") (pintype "passive"))
      (node (ref "IC1") (pin "5") (pinfunction "I_5") (pintype "input"))
      (node (ref "R12") (pin "2") (pinfunction "2_2") (pintype "passive"))
    )
    (net (code "35") (name "Net-(IC1F-O)") (class "Default")
      (node (ref "IC1") (pin "6") (pinfunction "O_6") (pintype "output"))
      (node (ref "IC7") (pin "5") (pinfunction "G_5") (pintype "input"))
    )
    (net (code "36") (name "Net-(IC2A-I)") (class "Default")
      (node (ref "C7") (pin "+") (pinfunction "+_+") (pintype "passive"))
      (node (ref "IC2") (pin "13") (pinfunction "I_13") (pintype "input"))
      (node (ref "R14") (pin "2") (pinfunction "2_2") (pintype "passive"))
    )
    (net (code "37") (name "Net-(IC2A-O)") (class "Default")
      (node (ref "IC2") (pin "12") (pinfunction "O_12") (pintype "output"))
      (node (ref "IC7") (pin "4") (pinfunction "F_4") (pintype "input"))
    )
    (net (code "38") (name "Net-(IC2B-I)") (class "Default")
      (node (ref "C8") (pin "+") (pinfunction "+_+") (pintype "passive"))
      (node (ref "IC2") (pin "11") (pinfunction "I_11") (pintype "input"))
      (node (ref "R16") (pin "2") (pinfunction "2_2") (pintype "passive"))
    )
    (net (code "39") (name "Net-(IC2B-O)") (class "Default")
      (node (ref "IC2") (pin "10") (pinfunction "O_10") (pintype "output"))
      (node (ref "IC7") (pin "3") (pinfunction "E_3") (pintype "input"))
    )
    (net (code "40") (name "Net-(IC2C-I)") (class "Default")
      (node (ref "C9") (pin "+") (pinfunction "+_+") (pintype "passive"))
      (node (ref "IC2") (pin "9") (pinfunction "I_9") (pintype "input"))
      (node (ref "R18") (pin "2") (pinfunction "2_2") (pintype "passive"))
    )
    (net (code "41") (name "Net-(IC2C-O)") (class "Default")
      (node (ref "IC2") (pin "8") (pinfunction "O_8") (pintype "output"))
      (node (ref "IC7") (pin "14") (pinfunction "D_14") (pintype "input"))
    )
    (net (code "42") (name "Net-(IC2D-I)") (class "Default")
      (node (ref "C10") (pin "+") (pinfunction "+_+") (pintype "passive"))
      (node (ref "IC2") (pin "1") (pinfunction "I_1") (pintype "input"))
      (node (ref "R20") (pin "2") (pinfunction "2_2") (pintype "passive"))
    )
    (net (code "43") (name "Net-(IC2D-O)") (class "Default")
      (node (ref "IC2") (pin "2") (pinfunction "O_2") (pintype "output"))
      (node (ref "IC7") (pin "13") (pinfunction "C_13") (pintype "input"))
    )
    (net (code "44") (name "Net-(IC2E-I)") (class "Default")
      (node (ref "C11") (pin "+") (pinfunction "+_+") (pintype "passive"))
      (node (ref "IC2") (pin "3") (pinfunction "I_3") (pintype "input"))
      (node (ref "R22") (pin "2") (pinfunction "2_2") (pintype "passive"))
    )
    (net (code "45") (name "Net-(IC2E-O)") (class "Default")
      (node (ref "IC2") (pin "4") (pinfunction "O_4") (pintype "output"))
      (node (ref "IC7") (pin "12") (pinfunction "B_12") (pintype "input"))
    )
    (net (code "46") (name "Net-(IC2F-I)") (class "Default")
      (node (ref "C12") (pin "+") (pinfunction "+_+") (pintype "passive"))
      (node (ref "IC2") (pin "5") (pinfunction "I_5") (pintype "input"))
      (node (ref "R24") (pin "2") (pinfunction "2_2") (pintype "passive"))
    )
    (net (code "47") (name "Net-(IC2F-O)") (class "Default")
      (node (ref "IC2") (pin "6") (pinfunction "O_6") (pintype "output"))
      (node (ref "IC7") (pin "11") (pinfunction "A_11") (pintype "input"))
    )
    (net (code "48") (name "Net-(IC3A-I)") (class "Default")
      (node (ref "C13") (pin "+") (pinfunction "+_+") (pintype "passive"))
      (node (ref "IC3") (pin "13") (pinfunction "I_13") (pintype "input"))
      (node (ref "R26") (pin "2") (pinfunction "2_2") (pintype "passive"))
    )
    (net (code "49") (name "Net-(IC3A-O)") (class "Default")
      (node (ref "IC3") (pin "12") (pinfunction "O_12") (pintype "output"))
      (node (ref "IC9") (pin "6") (pinfunction "H_6") (pintype "input"))
    )
    (net (code "50") (name "Net-(IC3B-I)") (class "Default")
      (node (ref "C14") (pin "+") (pinfunction "+_+") (pintype "passive"))
      (node (ref "IC3") (pin "11") (pinfunction "I_11") (pintype "input"))
      (node (ref "R28") (pin "2") (pinfunction "2_2") (pintype "passive"))
    )
    (net (code "51") (name "Net-(IC3B-O)") (class "Default")
      (node (ref "IC3") (pin "10") (pinfunction "O_10") (pintype "output"))
      (node (ref "IC9") (pin "5") (pinfunction "G_5") (pintype "input"))
    )
    (net (code "52") (name "Net-(IC3C-I)") (class "Default")
      (node (ref "C15") (pin "+") (pinfunction "+_+") (pintype "passive"))
      (node (ref "IC3") (pin "9") (pinfunction "I_9") (pintype "input"))
      (node (ref "R30") (pin "2") (pinfunction "2_2") (pintype "passive"))
    )
    (net (code "53") (name "Net-(IC3C-O)") (class "Default")
      (node (ref "IC3") (pin "8") (pinfunction "O_8") (pintype "output"))
      (node (ref "IC9") (pin "4") (pinfunction "F_4") (pintype "input"))
    )
    (net (code "54") (name "Net-(IC3D-I)") (class "Default")
      (node (ref "C16") (pin "+") (pinfunction "+_+") (pintype "passive"))
      (node (ref "IC3") (pin "1") (pinfunction "I_1") (pintype "input"))
      (node (ref "R32") (pin "2") (pinfunction "2_2") (pintype "passive"))
    )
    (net (code "55") (name "Net-(IC3D-O)") (class "Default")
      (node (ref "IC3") (pin "2") (pinfunction "O_2") (pintype "output"))
      (node (ref "IC9") (pin "3") (pinfunction "E_3") (pintype "input"))
    )
    (net (code "56") (name "Net-(IC3E-I)") (class "Default")
      (node (ref "C17") (pin "+") (pinfunction "+_+") (pintype "passive"))
      (node (ref "IC3") (pin "3") (pinfunction "I_3") (pintype "input"))
      (node (ref "R34") (pin "2") (pinfunction "2_2") (pintype "passive"))
    )
    (net (code "57") (name "Net-(IC3E-O)") (class "Default")
      (node (ref "IC3") (pin "4") (pinfunction "O_4") (pintype "output"))
      (node (ref "IC9") (pin "14") (pinfunction "D_14") (pintype "input"))
    )
    (net (code "58") (name "Net-(IC3F-I)") (class "Default")
      (node (ref "C18") (pin "+") (pinfunction "+_+") (pintype "passive"))
      (node (ref "IC3") (pin "5") (pinfunction "I_5") (pintype "input"))
      (node (ref "R36") (pin "2") (pinfunction "2_2") (pintype "passive"))
    )
    (net (code "59") (name "Net-(IC3F-O)") (class "Default")
      (node (ref "IC3") (pin "6") (pinfunction "O_6") (pintype "output"))
      (node (ref "IC9") (pin "13") (pinfunction "C_13") (pintype "input"))
    )
    (net (code "60") (name "Net-(IC4A-I)") (class "Default")
      (node (ref "C19") (pin "+") (pinfunction "+_+") (pintype "passive"))
      (node (ref "IC4") (pin "13") (pinfunction "I_13") (pintype "input"))
      (node (ref "R38") (pin "2") (pinfunction "2_2") (pintype "passive"))
    )
    (net (code "61") (name "Net-(IC4A-O)") (class "Default")
      (node (ref "IC4") (pin "12") (pinfunction "O_12") (pintype "output"))
      (node (ref "IC9") (pin "12") (pinfunction "B_12") (pintype "input"))
    )
    (net (code "62") (name "Net-(IC4B-I)") (class "Default")
      (node (ref "C20") (pin "+") (pinfunction "+_+") (pintype "passive"))
      (node (ref "IC4") (pin "11") (pinfunction "I_11") (pintype "input"))
      (node (ref "R40") (pin "2") (pinfunction "2_2") (pintype "passive"))
    )
    (net (code "63") (name "Net-(IC4B-O)") (class "Default")
      (node (ref "IC4") (pin "10") (pinfunction "O_10") (pintype "output"))
      (node (ref "IC9") (pin "11") (pinfunction "A_11") (pintype "input"))
    )
    (net (code "64") (name "Net-(IC4C-I)") (class "Default")
      (node (ref "C21") (pin "+") (pinfunction "+_+") (pintype "passive"))
      (node (ref "IC4") (pin "9") (pinfunction "I_9") (pintype "input"))
      (node (ref "R42") (pin "2") (pinfunction "2_2") (pintype "passive"))
    )
    (net (code "65") (name "Net-(IC4C-O)") (class "Default")
      (node (ref "IC4") (pin "8") (pinfunction "O_8") (pintype "output"))
      (node (ref "IC8") (pin "6") (pinfunction "H_6") (pintype "input"))
    )
    (net (code "66") (name "Net-(IC4D-I)") (class "Default")
      (node (ref "C22") (pin "+") (pinfunction "+_+") (pintype "passive"))
      (node (ref "IC4") (pin "1") (pinfunction "I_1") (pintype "input"))
      (node (ref "R44") (pin "2") (pinfunction "2_2") (pintype "passive"))
    )
    (net (code "67") (name "Net-(IC4D-O)") (class "Default")
      (node (ref "IC4") (pin "2") (pinfunction "O_2") (pintype "output"))
      (node (ref "IC8") (pin "5") (pinfunction "G_5") (pintype "input"))
    )
    (net (code "68") (name "Net-(IC4E-I)") (class "Default")
      (node (ref "C23") (pin "+") (pinfunction "+_+") (pintype "passive"))
      (node (ref "IC4") (pin "3") (pinfunction "I_3") (pintype "input"))
      (node (ref "R46") (pin "2") (pinfunction "2_2") (pintype "passive"))
    )
    (net (code "69") (name "Net-(IC4E-O)") (class "Default")
      (node (ref "IC4") (pin "4") (pinfunction "O_4") (pintype "output"))
      (node (ref "IC8") (pin "4") (pinfunction "F_4") (pintype "input"))
    )
    (net (code "70") (name "Net-(IC4F-I)") (class "Default")
      (node (ref "C24") (pin "+") (pinfunction "+_+") (pintype "passive"))
      (node (ref "IC4") (pin "5") (pinfunction "I_5") (pintype "input"))
      (node (ref "R48") (pin "2") (pinfunction "2_2") (pintype "passive"))
    )
    (net (code "71") (name "Net-(IC4F-O)") (class "Default")
      (node (ref "IC4") (pin "6") (pinfunction "O_6") (pintype "output"))
      (node (ref "IC8") (pin "3") (pinfunction "E_3") (pintype "input"))
    )
    (net (code "72") (name "Net-(IC5A-I)") (class "Default")
      (node (ref "C25") (pin "+") (pinfunction "+_+") (pintype "passive"))
      (node (ref "IC5") (pin "13") (pinfunction "I_13") (pintype "input"))
      (node (ref "R50") (pin "2") (pinfunction "2_2") (pintype "passive"))
    )
    (net (code "73") (name "Net-(IC5B-I)") (class "Default")
      (node (ref "C26") (pin "+") (pinfunction "+_+") (pintype "passive"))
      (node (ref "IC5") (pin "11") (pinfunction "I_11") (pintype "input"))
      (node (ref "R52") (pin "2") (pinfunction "2_2") (pintype "passive"))
    )
    (net (code "74") (name "Net-(IC5C-I)") (class "Default")
      (node (ref "C27") (pin "+") (pinfunction "+_+") (pintype "passive"))
      (node (ref "IC5") (pin "9") (pinfunction "I_9") (pintype "input"))
      (node (ref "R54") (pin "2") (pinfunction "2_2") (pintype "passive"))
    )
    (net (code "75") (name "Net-(IC5D-I)") (class "Default")
      (node (ref "C28") (pin "+") (pinfunction "+_+") (pintype "passive"))
      (node (ref "IC5") (pin "1") (pinfunction "I_1") (pintype "input"))
      (node (ref "R56") (pin "2") (pinfunction "2_2") (pintype "passive"))
    )
    (net (code "76") (name "Net-(IC5E-I)") (class "Default")
      (node (ref "C29") (pin "+") (pinfunction "+_+") (pintype "passive"))
      (node (ref "IC5") (pin "3") (pinfunction "I_3") (pintype "input"))
      (node (ref "R58") (pin "2") (pinfunction "2_2") (pintype "passive"))
    )
    (net (code "77") (name "Net-(IC5F-I)") (class "Default")
      (node (ref "C30") (pin "+") (pinfunction "+_+") (pintype "passive"))
      (node (ref "IC5") (pin "5") (pinfunction "I_5") (pintype "input"))
      (node (ref "R60") (pin "2") (pinfunction "2_2") (pintype "passive"))
    )
    (net (code "78") (name "Net-(IC6A-I)") (class "Default")
      (node (ref "C31") (pin "+") (pinfunction "+_+") (pintype "passive"))
      (node (ref "IC6") (pin "13") (pinfunction "I_13") (pintype "input"))
      (node (ref "R62") (pin "2") (pinfunction "2_2") (pintype "passive"))
    )
    (net (code "79") (name "Net-(IC6B-I)") (class "Default")
      (node (ref "C32") (pin "+") (pinfunction "+_+") (pintype "passive"))
      (node (ref "IC6") (pin "11") (pinfunction "I_11") (pintype "input"))
      (node (ref "R64") (pin "2") (pinfunction "2_2") (pintype "passive"))
    )
    (net (code "80") (name "Net-(IC6C-I)") (class "Default")
      (node (ref "C33") (pin "+") (pinfunction "+_+") (pintype "passive"))
      (node (ref "IC6") (pin "9") (pinfunction "I_9") (pintype "input"))
      (node (ref "R66") (pin "2") (pinfunction "2_2") (pintype "passive"))
    )
    (net (code "81") (name "Net-(IC6D-I)") (class "Default")
      (node (ref "C34") (pin "+") (pinfunction "+_+") (pintype "passive"))
      (node (ref "IC6") (pin "1") (pinfunction "I_1") (pintype "input"))
      (node (ref "R68") (pin "2") (pinfunction "2_2") (pintype "passive"))
    )
    (net (code "82") (name "Net-(IC6E-I)") (class "Default")
      (node (ref "C35") (pin "+") (pinfunction "+_+") (pintype "passive"))
      (node (ref "IC6") (pin "3") (pinfunction "I_3") (pintype "input"))
      (node (ref "R70") (pin "2") (pinfunction "2_2") (pintype "passive"))
    )
    (net (code "83") (name "Net-(IC6F-I)") (class "Default")
      (node (ref "C36") (pin "+") (pinfunction "+_+") (pintype "passive"))
      (node (ref "IC6") (pin "5") (pinfunction "I_5") (pintype "input"))
      (node (ref "R72") (pin "2") (pinfunction "2_2") (pintype "passive"))
    )
    (net (code "84") (name "Net-(IC7A-QH)") (class "Default")
      (node (ref "IC7") (pin "9") (pinfunction "QH_9") (pintype "output"))
      (node (ref "IC8") (pin "10") (pinfunction "SER_10") (pintype "input"))
    )
    (net (code "85") (name "Net-(IC7A-SER)") (class "Default")
      (node (ref "EXTEND") (pin "3") (pinfunction "3_3") (pintype "passive"))
      (node (ref "IC7") (pin "10") (pinfunction "SER_10") (pintype "input"))
    )
    (net (code "86") (name "Net-(IC8A-QH)") (class "Default")
      (node (ref "IC8") (pin "9") (pinfunction "QH_9") (pintype "output"))
      (node (ref "IC9") (pin "10") (pinfunction "SER_10") (pintype "input"))
    )
    (net (code "87") (name "Net-(IC10A-A)") (class "Default")
      (node (ref "IC10") (pin "11") (pinfunction "A_11") (pintype "input"))
      (node (ref "IC6") (pin "6") (pinfunction "O_6") (pintype "output"))
    )
    (net (code "88") (name "Net-(IC10A-B)") (class "Default")
      (node (ref "IC10") (pin "12") (pinfunction "B_12") (pintype "input"))
      (node (ref "IC6") (pin "4") (pinfunction "O_4") (pintype "output"))
    )
    (net (code "89") (name "Net-(IC10A-C)") (class "Default")
      (node (ref "IC10") (pin "13") (pinfunction "C_13") (pintype "input"))
      (node (ref "IC6") (pin "2") (pinfunction "O_2") (pintype "output"))
    )
    (net (code "90") (name "Net-(IC10A-D)") (class "Default")
      (node (ref "IC10") (pin "14") (pinfunction "D_14") (pintype "input"))
      (node (ref "IC6") (pin "8") (pinfunction "O_8") (pintype "output"))
    )
    (net (code "91") (name "Net-(IC10A-E)") (class "Default")
      (node (ref "IC10") (pin "3") (pinfunction "E_3") (pintype "input"))
      (node (ref "IC6") (pin "10") (pinfunction "O_10") (pintype "output"))
    )
    (net (code "92") (name "Net-(IC10A-F)") (class "Default")
      (node (ref "IC10") (pin "4") (pinfunction "F_4") (pintype "input"))
      (node (ref "IC6") (pin "12") (pinfunction "O_12") (pintype "output"))
    )
    (net (code "93") (name "Net-(IC10A-G)") (class "Default")
      (node (ref "IC10") (pin "5") (pinfunction "G_5") (pintype "input"))
      (node (ref "IC5") (pin "6") (pinfunction "O_6") (pintype "output"))
    )
    (net (code "94") (name "Net-(IC10A-H)") (class "Default")
      (node (ref "IC10") (pin "6") (pinfunction "H_6") (pintype "input"))
      (node (ref "IC5") (pin "4") (pinfunction "O_4") (pintype "output"))
    )
    (net (code "95") (name "Net-(IC10A-SER)") (class "Default")
      (node (ref "IC10") (pin "10") (pinfunction "SER_10") (pintype "input"))
      (node (ref "IC9") (pin "9") (pinfunction "QH_9") (pintype "output"))
    )
    (net (code "96") (name "Net-(IC11-PB6(XTAL1{slash}TOSC1{slash}PCINT6))") (class "Default")
      (node (ref "C39") (pin "2") (pinfunction "2_2") (pintype "passive"))
      (node (ref "IC11") (pin "9") (pinfunction "PB6(XTAL1/TOSC1/PCINT6)_9") (pintype "bidirectional"))
      (node (ref "Q1") (pin "2") (pinfunction "2_2") (pintype "passive"))
    )
    (net (code "97") (name "Net-(IC11-PB7(XTAL2{slash}TOSC2{slash}PCINT7))") (class "Default")
      (node (ref "C38") (pin "2") (pinfunction "2_2") (pintype "passive"))
      (node (ref "IC11") (pin "10") (pinfunction "PB7(XTAL2/TOSC2/PCINT7)_10") (pintype "bidirectional"))
      (node (ref "Q1") (pin "1") (pinfunction "1_1") (pintype "passive"))
    )
    (net (code "98") (name "Net-(JP1-Pad2)") (class "Default")
      (node (ref "JP1") (pin "2") (pinfunction "2_2") (pintype "passive"))
      (node (ref "R1") (pin "2") (pinfunction "2_2") (pintype "passive"))
      (node (ref "R2") (pin "1") (pinfunction "1_1") (pintype "passive"))
    )
    (net (code "99") (name "Net-(JP2-Pad2)") (class "Default")
      (node (ref "JP2") (pin "2") (pinfunction "2_2") (pintype "passive"))
      (node (ref "R3") (pin "2") (pinfunction "2_2") (pintype "passive"))
      (node (ref "R4") (pin "1") (pinfunction "1_1") (pintype "passive"))
    )
    (net (code "100") (name "Net-(JP3-Pad2)") (class "Default")
      (node (ref "JP3") (pin "2") (pinfunction "2_2") (pintype "passive"))
      (node (ref "R5") (pin "2") (pinfunction "2_2") (pintype "passive"))
      (node (ref "R6") (pin "1") (pinfunction "1_1") (pintype "passive"))
    )
    (net (code "101") (name "Net-(JP4-Pad2)") (class "Default")
      (node (ref "JP4") (pin "2") (pinfunction "2_2") (pintype "passive"))
      (node (ref "R7") (pin "2") (pinfunction "2_2") (pintype "passive"))
      (node (ref "R8") (pin "1") (pinfunction "1_1") (pintype "passive"))
    )
    (net (code "102") (name "Net-(JP5-Pad2)") (class "Default")
      (node (ref "JP5") (pin "2") (pinfunction "2_2") (pintype "passive"))
      (node (ref "R10") (pin "1") (pinfunction "1_1") (pintype "passive"))
      (node (ref "R9") (pin "2") (pinfunction "2_2") (pintype "passive"))
    )
    (net (code "103") (name "Net-(JP6-Pad2)") (class "Default")
      (node (ref "JP6") (pin "2") (pinfunction "2_2") (pintype "passive"))
      (node (ref "R11") (pin "2") (pinfunction "2_2") (pintype "passive"))
      (node (ref "R12") (pin "1") (pinfunction "1_1") (pintype "passive"))
    )
    (net (code "104") (name "Net-(JP7-Pad2)") (class "Default")
      (node (ref "JP7") (pin "2") (pinfunction "2_2") (pintype "passive"))
      (node (ref "R13") (pin "2") (pinfunction "2_2") (pintype "passive"))
      (node (ref "R14") (pin "1") (pinfunction "1_1") (pintype "passive"))
    )
    (net (code "105") (name "Net-(JP8-Pad2)") (class "Default")
      (node (ref "JP8") (pin "2") (pinfunction "2_2") (pintype "passive"))
      (node (ref "R15") (pin "2") (pinfunction "2_2") (pintype "passive"))
      (node (ref "R16") (pin "1") (pinfunction "1_1") (pintype "passive"))
    )
    (net (code "106") (name "Net-(JP9-Pad2)") (class "Default")
      (node (ref "JP9") (pin "2") (pinfunction "2_2") (pintype "passive"))
      (node (ref "R17") (pin "2") (pinfunction "2_2") (pintype "passive"))
      (node (ref "R18") (pin "1") (pinfunction "1_1") (pintype "passive"))
    )
    (net (code "107") (name "Net-(JP10-Pad2)") (class "Default")
      (node (ref "JP10") (pin "2") (pinfunction "2_2") (pintype "passive"))
      (node (ref "R19") (pin "2") (pinfunction "2_2") (pintype "passive"))
      (node (ref "R20") (pin "1") (pinfunction "1_1") (pintype "passive"))
    )
    (net (code "108") (name "Net-(JP11-Pad2)") (class "Default")
      (node (ref "JP11") (pin "2") (pinfunction "2_2") (pintype "passive"))
      (node (ref "R21") (pin "2") (pinfunction "2_2") (pintype "passive"))
      (node (ref "R22") (pin "1") (pinfunction "1_1") (pintype "passive"))
    )
    (net (code "109") (name "Net-(JP12-Pad2)") (class "Default")
      (node (ref "JP12") (pin "2") (pinfunction "2_2") (pintype "passive"))
      (node (ref "R23") (pin "2") (pinfunction "2_2") (pintype "passive"))
      (node (ref "R24") (pin "1") (pinfunction "1_1") (pintype "passive"))
    )
    (net (code "110") (name "Net-(JP13-Pad2)") (class "Default")
      (node (ref "JP13") (pin "2") (pinfunction "2_2") (pintype "passive"))
      (node (ref "R25") (pin "2") (pinfunction "2_2") (pintype "passive"))
      (node (ref "R26") (pin "1") (pinfunction "1_1") (pintype "passive"))
    )
    (net (code "111") (name "Net-(JP14-Pad2)") (class "Default")
      (node (ref "JP14") (pin "2") (pinfunction "2_2") (pintype "passive"))
      (node (ref "R27") (pin "2") (pinfunction "2_2") (pintype "passive"))
      (node (ref "R28") (pin "1") (pinfunction "1_1") (pintype "passive"))
    )
    (net (code "112") (name "Net-(JP15-Pad2)") (class "Default")
      (node (ref "JP15") (pin "2") (pinfunction "2_2") (pintype "passive"))
      (node (ref "R29") (pin "2") (pinfunction "2_2") (pintype "passive"))
      (node (ref "R30") (pin "1") (pinfunction "1_1") (pintype "passive"))
    )
    (net (code "113") (name "Net-(JP16-Pad2)") (class "Default")
      (node (ref "JP16") (pin "2") (pinfunction "2_2") (pintype "passive"))
      (node (ref "R31") (pin "2") (pinfunction "2_2") (pintype "passive"))
      (node (ref "R32") (pin "1") (pinfunction "1_1") (pintype "passive"))
    )
    (net (code "114") (name "Net-(JP17-Pad2)") (class "Default")
      (node (ref "JP17") (pin "2") (pinfunction "2_2") (pintype "passive"))
      (node (ref "R33") (pin "2") (pinfunction "2_2") (pintype "passive"))
      (node (ref "R34") (pin "1") (pinfunction "1_1") (pintype "passive"))
    )
    (net (code "115") (name "Net-(JP18-Pad2)") (class "Default")
      (node (ref "JP18") (pin "2") (pinfunction "2_2") (pintype "passive"))
      (node (ref "R35") (pin "2") (pinfunction "2_2") (pintype "passive"))
      (node (ref "R36") (pin "1") (pinfunction "1_1") (pintype "passive"))
    )
    (net (code "116") (name "Net-(JP19-Pad2)") (class "Default")
      (node (ref "JP19") (pin "2") (pinfunction "2_2") (pintype "passive"))
      (node (ref "R37") (pin "2") (pinfunction "2_2") (pintype "passive"))
      (node (ref "R38") (pin "1") (pinfunction "1_1") (pintype "passive"))
    )
    (net (code "117") (name "Net-(JP20-Pad2)") (class "Default")
      (node (ref "JP20") (pin "2") (pinfunction "2_2") (pintype "passive"))
      (node (ref "R39") (pin "2") (pinfunction "2_2") (pintype "passive"))
      (node (ref "R40") (pin "1") (pinfunction "1_1") (pintype "passive"))
    )
    (net (code "118") (name "Net-(JP21-Pad2)") (class "Default")
      (node (ref "JP21") (pin "2") (pinfunction "2_2") (pintype "passive"))
      (node (ref "R41") (pin "2") (pinfunction "2_2") (pintype "passive"))
      (node (ref "R42") (pin "1") (pinfunction "1_1") (pintype "passive"))
    )
    (net (code "119") (name "Net-(JP22-Pad2)") (class "Default")
      (node (ref "JP22") (pin "2") (pinfunction "2_2") (pintype "passive"))
      (node (ref "R43") (pin "2") (pinfunction "2_2") (pintype "passive"))
      (node (ref "R44") (pin "1") (pinfunction "1_1") (pintype "passive"))
    )
    (net (code "120") (name "Net-(JP23-Pad2)") (class "Default")
      (node (ref "JP23") (pin "2") (pinfunction "2_2") (pintype "passive"))
      (node (ref "R45") (pin "2") (pinfunction "2_2") (pintype "passive"))
      (node (ref "R46") (pin "1") (pinfunction "1_1") (pintype "passive"))
    )
    (net (code "121") (name "Net-(JP24-Pad2)") (class "Default")
      (node (ref "JP24") (pin "2") (pinfunction "2_2") (pintype "passive"))
      (node (ref "R47") (pin "2") (pinfunction "2_2") (pintype "passive"))
      (node (ref "R48") (pin "1") (pinfunction "1_1") (pintype "passive"))
    )
    (net (code "122") (name "Net-(JP25-Pad2)") (class "Default")
      (node (ref "JP25") (pin "2") (pinfunction "2_2") (pintype "passive"))
      (node (ref "R49") (pin "2") (pinfunction "2_2") (pintype "passive"))
      (node (ref "R50") (pin "1") (pinfunction "1_1") (pintype "passive"))
    )
    (net (code "123") (name "Net-(JP26-Pad2)") (class "Default")
      (node (ref "JP26") (pin "2") (pinfunction "2_2") (pintype "passive"))
      (node (ref "R51") (pin "2") (pinfunction "2_2") (pintype "passive"))
      (node (ref "R52") (pin "1") (pinfunction "1_1") (pintype "passive"))
    )
    (net (code "124") (name "Net-(JP27-Pad2)") (class "Default")
      (node (ref "JP27") (pin "2") (pinfunction "2_2") (pintype "passive"))
      (node (ref "R53") (pin "2") (pinfunction "2_2") (pintype "passive"))
      (node (ref "R54") (pin "1") (pinfunction "1_1") (pintype "passive"))
    )
    (net (code "125") (name "Net-(JP28-Pad2)") (class "Default")
      (node (ref "JP28") (pin "2") (pinfunction "2_2") (pintype "passive"))
      (node (ref "R55") (pin "2") (pinfunction "2_2") (pintype "passive"))
      (node (ref "R56") (pin "1") (pinfunction "1_1") (pintype "passive"))
    )
    (net (code "126") (name "Net-(JP29-Pad2)") (class "Default")
      (node (ref "JP29") (pin "2") (pinfunction "2_2") (pintype "passive"))
      (node (ref "R57") (pin "2") (pinfunction "2_2") (pintype "passive"))
      (node (ref "R58") (pin "1") (pinfunction "1_1") (pintype "passive"))
    )
    (net (code "127") (name "Net-(JP30-Pad2)") (class "Default")
      (node (ref "JP30") (pin "2") (pinfunction "2_2") (pintype "passive"))
      (node (ref "R59") (pin "2") (pinfunction "2_2") (pintype "passive"))
      (node (ref "R60") (pin "1") (pinfunction "1_1") (pintype "passive"))
    )
    (net (code "128") (name "Net-(JP31-Pad2)") (class "Default")
      (node (ref "JP31") (pin "2") (pinfunction "2_2") (pintype "passive"))
      (node (ref "R61") (pin "2") (pinfunction "2_2") (pintype "passive"))
      (node (ref "R62") (pin "1") (pinfunction "1_1") (pintype "passive"))
    )
    (net (code "129") (name "Net-(JP32-Pad2)") (class "Default")
      (node (ref "JP32") (pin "2") (pinfunction "2_2") (pintype "passive"))
      (node (ref "R63") (pin "2") (pinfunction "2_2") (pintype "passive"))
      (node (ref "R64") (pin "1") (pinfunction "1_1") (pintype "passive"))
    )
    (net (code "130") (name "Net-(JP33-Pad2)") (class "Default")
      (node (ref "JP33") (pin "2") (pinfunction "2_2") (pintype "passive"))
      (node (ref "R65") (pin "2") (pinfunction "2_2") (pintype "passive"))
      (node (ref "R66") (pin "1") (pinfunction "1_1") (pintype "passive"))
    )
    (net (code "131") (name "Net-(JP34-Pad2)") (class "Default")
      (node (ref "JP34") (pin "2") (pinfunction "2_2") (pintype "passive"))
      (node (ref "R67") (pin "2") (pinfunction "2_2") (pintype "passive"))
      (node (ref "R68") (pin "1") (pinfunction "1_1") (pintype "passive"))
    )
    (net (code "132") (name "Net-(JP35-Pad2)") (class "Default")
      (node (ref "JP35") (pin "2") (pinfunction "2_2") (pintype "passive"))
      (node (ref "R69") (pin "2") (pinfunction "2_2") (pintype "passive"))
      (node (ref "R70") (pin "1") (pinfunction "1_1") (pintype "passive"))
    )
    (net (code "133") (name "Net-(JP36-Pad2)") (class "Default")
      (node (ref "JP36") (pin "2") (pinfunction "2_2") (pintype "passive"))
      (node (ref "R71") (pin "2") (pinfunction "2_2") (pintype "passive"))
      (node (ref "R72") (pin "1") (pinfunction "1_1") (pintype "passive"))
    )
    (net (code "134") (name "Net-(LCKLED_OUT-Pad1)") (class "Default")
      (node (ref "LCKLED_OUT") (pin "1") (pinfunction "1_1") (pintype "passive"))
      (node (ref "R74") (pin "1") (pinfunction "1_1") (pintype "passive"))
    )
    (net (code "135") (name "VCC") (class "Default")
      (node (ref "C37") (pin "1") (pinfunction "1_1") (pintype "passive"))
      (node (ref "EXTEND") (pin "4") (pinfunction "4_4") (pintype "passive"))
      (node (ref "IC1") (pin "14") (pinfunction "VCC_14") (pintype "power_in"))
      (node (ref "IC10") (pin "16") (pinfunction "VCC_16") (pintype "power_in"))
      (node (ref "IC11") (pin "20") (pinfunction "AVCC_20") (pintype "passive"))
      (node (ref "IC11") (pin "21") (pinfunction "AREF_21") (pintype "passive"))
      (node (ref "IC11") (pin "7") (pinfunction "VCC_7") (pintype "power_in"))
      (node (ref "IC2") (pin "14") (pinfunction "VCC_14") (pintype "power_in"))
      (node (ref "IC3") (pin "14") (pinfunction "VCC_14") (pintype "power_in"))
      (node (ref "IC4") (pin "14") (pinfunction "VCC_14") (pintype "power_in"))
      (node (ref "IC5") (pin "14") (pinfunction "VCC_14") (pintype "power_in"))
      (node (ref "IC6") (pin "14") (pinfunction "VCC_14") (pintype "power_in"))
      (node (ref "IC7") (pin "16") (pinfunction "VCC_16") (pintype "power_in"))
      (node (ref "IC8") (pin "16") (pinfunction "VCC_16") (pintype "power_in"))
      (node (ref "IC9") (pin "16") (pinfunction "VCC_16") (pintype "power_in"))
      (node (ref "ISP") (pin "2") (pinfunction "2_2") (pintype "passive"))
      (node (ref "JRX") (pin "2") (pinfunction "2_2") (pintype "passive"))
      (node (ref "JRY") (pin "2") (pinfunction "2_2") (pintype "passive"))
      (node (ref "JRZ") (pin "2") (pinfunction "2_2") (pintype "passive"))
      (node (ref "JX") (pin "2") (pinfunction "2_2") (pintype "passive"))
      (node (ref "JY") (pin "2") (pinfunction "2_2") (pintype "passive"))
      (node (ref "JZ") (pin "2") (pinfunction "2_2") (pintype "passive"))
      (node (ref "LED2") (pin "A") (pinfunction "A_A") (pintype "passive"))
      (node (ref "R1") (pin "1") (pinfunction "1_1") (pintype "passive"))
      (node (ref "R11") (pin "1") (pinfunction "1_1") (pintype "passive"))
      (node (ref "R13") (pin "1") (pinfunction "1_1") (pintype "passive"))
      (node (ref "R15") (pin "1") (pinfunction "1_1") (pintype "passive"))
      (node (ref "R17") (pin "1") (pinfunction "1_1") (pintype "passive"))
      (node (ref "R19") (pin "1") (pinfunction "1_1") (pintype "passive"))
      (node (ref "R21") (pin "1") (pinfunction "1_1") (pintype "passive"))
      (node (ref "R23") (pin "1") (pinfunction "1_1") (pintype "passive"))
      (node (ref "R25") (pin "1") (pinfunction "1_1") (pintype "passive"))
      (node (ref "R27") (pin "1") (pinfunction "1_1") (pintype "passive"))
      (node (ref "R29") (pin "1") (pinfunction "1_1") (pintype "passive"))
      (node (ref "R3") (pin "1") (pinfunction "1_1") (pintype "passive"))
      (node (ref "R31") (pin "1") (pinfunction "1_1") (pintype "passive"))
      (node (ref "R33") (pin "1") (pinfunction "1_1") (pintype "passive"))
      (node (ref "R35") (pin "1") (pinfunction "1_1") (pintype "passive"))
      (node (ref "R37") (pin "1") (pinfunction "1_1") (pintype "passive"))
      (node (ref "R39") (pin "1") (pinfunction "1_1") (pintype "passive"))
      (node (ref "R41") (pin "1") (pinfunction "1_1") (pintype "passive"))
      (node (ref "R43") (pin "1") (pinfunction "1_1") (pintype "passive"))
      (node (ref "R45") (pin "1") (pinfunction "1_1") (pintype "passive"))
      (node (ref "R47") (pin "1") (pinfunction "1_1") (pintype "passive"))
      (node (ref "R49") (pin "1") (pinfunction "1_1") (pintype "passive"))
      (node (ref "R5") (pin "1") (pinfunction "1_1") (pintype "passive"))
      (node (ref "R51") (pin "1") (pinfunction "1_1") (pintype "passive"))
      (node (ref "R53") (pin "1") (pinfunction "1_1") (pintype "passive"))
      (node (ref "R55") (pin "1") (pinfunction "1_1") (pintype "passive"))
      (node (ref "R57") (pin "1") (pinfunction "1_1") (pintype "passive"))
      (node (ref "R59") (pin "1") (pinfunction "1_1") (pintype "passive"))
      (node (ref "R61") (pin "1") (pinfunction "1_1") (pintype "passive"))
      (node (ref "R63") (pin "1") (pinfunction "1_1") (pintype "passive"))
      (node (ref "R65") (pin "1") (pinfunction "1_1") (pintype "passive"))
      (node (ref "R67") (pin "1") (pinfunction "1_1") (pintype "passive"))
      (node (ref "R69") (pin "1") (pinfunction "1_1") (pintype "passive"))
      (node (ref "R7") (pin "1") (pinfunction "1_1") (pintype "passive"))
      (node (ref "R71") (pin "1") (pinfunction "1_1") (pintype "passive"))
      (node (ref "R73") (pin "1") (pinfunction "1_1") (pintype "passive"))
      (node (ref "R75") (pin "1") (pinfunction "1_1") (pintype "passive"))
      (node (ref "R9") (pin "1") (pinfunction "1_1") (pintype "passive"))
    )
    (net (code "136") (name "unconnected-(IC7A-~{QH}-Pad7)") (class "Default")
      (node (ref "IC7") (pin "7") (pinfunction "~{QH}_7") (pintype "output"))
    )
    (net (code "137") (name "unconnected-(IC8A-~{QH}-Pad7)") (class "Default")
      (node (ref "IC8") (pin "7") (pinfunction "~{QH}_7") (pintype "output"))
    )
    (net (code "138") (name "unconnected-(IC9A-~{QH}-Pad7)") (class "Default")
      (node (ref "IC9") (pin "7") (pinfunction "~{QH}_7") (pintype "output"))
    )
    (net (code "139") (name "unconnected-(IC10A-~{QH}-Pad7)") (class "Default")
      (node (ref "IC10") (pin "7") (pinfunction "~{QH}_7") (pintype "output"))
    )
    (net (code "140") (name "unconnected-(IC11-PD0(RXD{slash}PCINT16)-Pad2)") (class "Default")
      (node (ref "IC11") (pin "2") (pinfunction "PD0(RXD/PCINT16)_2") (pintype "bidirectional"))
    )
    (net (code "141") (name "unconnected-(IC11-PD1(TXD{slash}PCINT17)-Pad3)") (class "Default")
      (node (ref "IC11") (pin "3") (pinfunction "PD1(TXD/PCINT17)_3") (pintype "bidirectional"))
    )
  )
)
